# power.net
KiCad netlist of a schematic drawn in Altium Designer
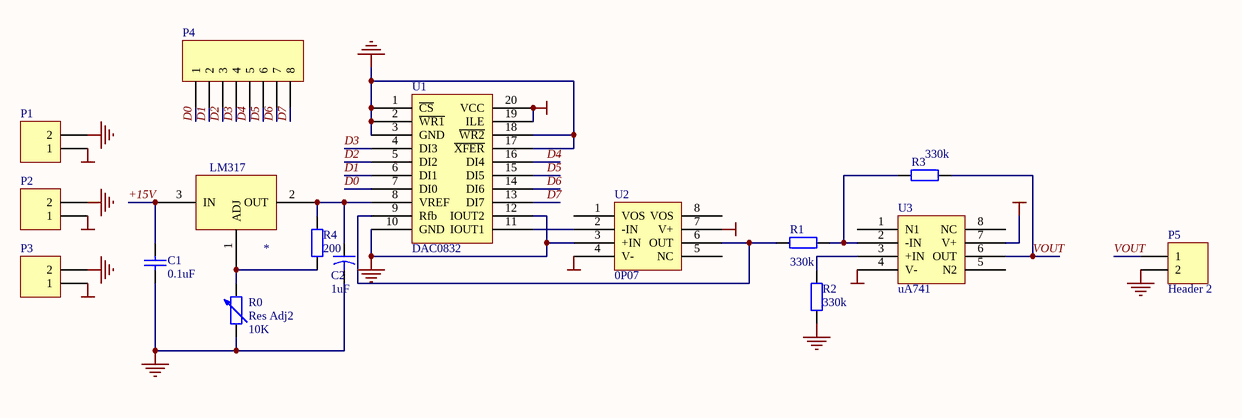
[diagram p0: power.SchDoc]

(export (version "E")
  (design (tool "Eeschema 10.0.6"))
  (components
    (comp (ref "C1")
      (value "0.1uF")
      (footprint "RAD-0.1")
      (description "Capacitor")
      (fields (field (name "PUBLISHER") "Altium Limited"))
      (libsource (lib "Miscellaneous Devices") (part "Cap"))
    )
    (comp (ref "C2")
      (value "1uF")
      (footprint "CAPR5-4X5")
      (description "Capacitor")
      (fields (field (name "PUBLISHER") "Altium Limited"))
      (libsource (lib "Miscellaneous Devices") (part "Cap2"))
    )
    (comp (ref "LM317") (value "*") (footprint "HDR1X3") (libsource (lib "My sch Library") (part "LM317")))
    (comp (ref "P1")
      (value "~")
      (footprint "HDR1X2")
      (description "Header, 2-Pin")
      (fields (field (name "PUBLISHER") "Altium Limited"))
      (libsource (lib "Miscellaneous Connectors") (part "Header 2"))
    )
    (comp (ref "P2")
      (value "~")
      (footprint "HDR1X2")
      (description "Header, 2-Pin")
      (fields (field (name "PUBLISHER") "Altium Limited"))
      (libsource (lib "Miscellaneous Connectors") (part "Header 2"))
    )
    (comp (ref "P3")
      (value "~")
      (footprint "HDR1X2")
      (description "Header, 2-Pin")
      (fields (field (name "PUBLISHER") "Altium Limited"))
      (libsource (lib "Miscellaneous Connectors") (part "Header 2"))
    )
    (comp (ref "P4")
      (value "~")
      (footprint "HDR1X8")
      (description "Header, 8-Pin")
      (fields (field (name "PUBLISHER") "Altium Limited"))
      (libsource (lib "Miscellaneous Connectors") (part "Header 8"))
    )
    (comp (ref "P5")
      (value "Header 2")
      (footprint "HDR1X2")
      (description "Header, 2-Pin")
      (fields (field (name "PUBLISHER") "Altium Limited"))
      (libsource (lib "") (part "Header 2_1"))
    )
    (comp (ref "R0")
      (value "Res Adj2")
      (footprint "AXIAL-0.6")
      (description "Variable Resistor")
      (fields (field (name "ALTIUM_VALUE") "10K") (field (name "PUBLISHER") "Altium Limited"))
      (libsource (lib "Miscellaneous Devices") (part "Res Adj2"))
    )
    (comp (ref "R1")
      (value "330k")
      (footprint "AXIAL-0.4")
      (description "Resistor")
      (fields (field (name "PUBLISHER") "Altium Limited"))
      (libsource (lib "") (part "Res2_1"))
    )
    (comp (ref "R2")
      (value "330k")
      (footprint "AXIAL-0.4")
      (description "Resistor")
      (fields (field (name "PUBLISHER") "Altium Limited"))
      (libsource (lib "Miscellaneous Devices") (part "Res2"))
    )
    (comp (ref "R3")
      (value "330k")
      (footprint "AXIAL-0.4")
      (description "Resistor")
      (fields (field (name "PUBLISHER") "Altium Limited"))
      (libsource (lib "") (part "Res2_1"))
    )
    (comp (ref "R4")
      (value "200")
      (footprint "AXIAL-0.4")
      (description "Resistor")
      (fields (field (name "PUBLISHER") "Altium Limited"))
      (libsource (lib "Miscellaneous Devices") (part "Res2"))
    )
    (comp (ref "U1")
      (value "DAC0832")
      (footprint "DIP-20")
      (libsource (lib "My sch Library") (part "DAC0832"))
    )
    (comp (ref "U2") (value "0P07") (footprint "DIP-8") (libsource (lib "My sch Library") (part "OP07")))
    (comp (ref "U3")
      (value "uA741")
      (footprint "DIP-8")
      (libsource (lib "My Integrated_Library") (part "uA741"))
    )
  )
  (nets
    (net (code "1") (name "+5V") (class "Default")
      (node (ref "P1") (pin "1") (pinfunction "1_1") (pintype "passive"))
      (node (ref "U1") (pin "19") (pinfunction "ILE_19") (pintype "passive"))
      (node (ref "U1") (pin "20") (pinfunction "VCC_20") (pintype "passive"))
    )
    (net (code "2") (name "+15V") (class "Default")
      (node (ref "C1") (pin "2") (pinfunction "2_2") (pintype "passive"))
      (node (ref "LM317") (pin "3") (pinfunction "IN_3") (pintype "passive"))
      (node (ref "P2") (pin "1") (pinfunction "1_1") (pintype "passive"))
      (node (ref "U2") (pin "7") (pinfunction "V+_7") (pintype "passive"))
      (node (ref "U3") (pin "7") (pinfunction "V+_7") (pintype "passive"))
    )
    (net (code "3") (name "-15V") (class "Default")
      (node (ref "P3") (pin "1") (pinfunction "1_1") (pintype "passive"))
      (node (ref "U2") (pin "4") (pinfunction "V-_4") (pintype "passive"))
      (node (ref "U3") (pin "4") (pinfunction "V-_4") (pintype "passive"))
    )
    (net (code "4") (name "/D0") (class "Default")
      (node (ref "P4") (pin "1") (pinfunction "1_1") (pintype "passive"))
      (node (ref "U1") (pin "7") (pinfunction "DI0_7") (pintype "passive"))
    )
    (net (code "5") (name "/D1") (class "Default")
      (node (ref "P4") (pin "2") (pinfunction "2_2") (pintype "passive"))
      (node (ref "U1") (pin "6") (pinfunction "DI1_6") (pintype "passive"))
    )
    (net (code "6") (name "/D2") (class "Default")
      (node (ref "P4") (pin "3") (pinfunction "3_3") (pintype "passive"))
      (node (ref "U1") (pin "5") (pinfunction "DI2_5") (pintype "passive"))
    )
    (net (code "7") (name "/D3") (class "Default")
      (node (ref "P4") (pin "4") (pinfunction "4_4") (pintype "passive"))
      (node (ref "U1") (pin "4") (pinfunction "DI3_4") (pintype "passive"))
    )
    (net (code "8") (name "/D4") (class "Default")
      (node (ref "P4") (pin "5") (pinfunction "5_5") (pintype "passive"))
      (node (ref "U1") (pin "16") (pinfunction "DI4_16") (pintype "passive"))
    )
    (net (code "9") (name "/D5") (class "Default")
      (node (ref "P4") (pin "6") (pinfunction "6_6") (pintype "passive"))
      (node (ref "U1") (pin "15") (pinfunction "DI5_15") (pintype "passive"))
    )
    (net (code "10") (name "/D6") (class "Default")
      (node (ref "P4") (pin "7") (pinfunction "7_7") (pintype "passive"))
      (node (ref "U1") (pin "14") (pinfunction "DI6_14") (pintype "passive"))
    )
    (net (code "11") (name "/D7") (class "Default")
      (node (ref "P4") (pin "8") (pinfunction "8_8") (pintype "passive"))
      (node (ref "U1") (pin "13") (pinfunction "DI7_13") (pintype "passive"))
    )
    (net (code "12") (name "/VOUT") (class "Default")
      (node (ref "P5") (pin "1") (pinfunction "1_1") (pintype "passive"))
      (node (ref "R3") (pin "2") (pinfunction "2_2") (pintype "passive"))
      (node (ref "U3") (pin "6") (pinfunction "OUT_6") (pintype "passive"))
    )
    (net (code "13") (name "GND") (class "Default")
      (node (ref "C1") (pin "1") (pinfunction "1_1") (pintype "passive"))
      (node (ref "C2") (pin "2") (pinfunction "2_2") (pintype "passive"))
      (node (ref "P1") (pin "2") (pinfunction "2_2") (pintype "passive"))
      (node (ref "P2") (pin "2") (pinfunction "2_2") (pintype "passive"))
      (node (ref "P3") (pin "2") (pinfunction "2_2") (pintype "passive"))
      (node (ref "P5") (pin "2") (pinfunction "2_2") (pintype "passive"))
      (node (ref "R0") (pin "1") (pinfunction "1_1") (pintype "passive"))
      (node (ref "R2") (pin "1") (pinfunction "1_1") (pintype "passive"))
      (node (ref "U1") (pin "1") (pinfunction "~{CS}_1") (pintype "passive"))
      (node (ref "U1") (pin "10") (pinfunction "GND_10") (pintype "passive"))
      (node (ref "U1") (pin "12") (pinfunction "IOUT2_12") (pintype "passive"))
      (node (ref "U1") (pin "17") (pinfunction "~{XFER}_17") (pintype "passive"))
      (node (ref "U1") (pin "18") (pinfunction "~{WR2}_18") (pintype "passive"))
      (node (ref "U1") (pin "2") (pinfunction "~{WR1}_2") (pintype "passive"))
      (node (ref "U1") (pin "3") (pinfunction "GND_3") (pintype "passive"))
      (node (ref "U2") (pin "3") (pinfunction "+IN_3") (pintype "passive"))
    )
    (net (code "14") (name "Net-(LM317-ADJ)") (class "Default")
      (node (ref "LM317") (pin "1") (pinfunction "ADJ_1") (pintype "passive"))
      (node (ref "R0") (pin "2") (pinfunction "2_2") (pintype "passive"))
      (node (ref "R4") (pin "1") (pinfunction "1_1") (pintype "passive"))
    )
    (net (code "15") (name "Net-(LM317-OUT)") (class "Default")
      (node (ref "C2") (pin "1") (pinfunction "1_1") (pintype "passive"))
      (node (ref "LM317") (pin "2") (pinfunction "OUT_2") (pintype "passive"))
      (node (ref "R4") (pin "2") (pinfunction "2_2") (pintype "passive"))
      (node (ref "U1") (pin "8") (pinfunction "VREF_8") (pintype "passive"))
    )
    (net (code "16") (name "Net-(U1-IOUT1)") (class "Default")
      (node (ref "U1") (pin "11") (pinfunction "IOUT1_11") (pintype "passive"))
      (node (ref "U2") (pin "2") (pinfunction "-IN_2") (pintype "passive"))
    )
    (net (code "17") (name "Net-(U1-Rfb)") (class "Default")
      (node (ref "R1") (pin "1") (pinfunction "1_1") (pintype "passive"))
      (node (ref "U1") (pin "9") (pinfunction "Rfb_9") (pintype "passive"))
      (node (ref "U2") (pin "6") (pinfunction "OUT_6") (pintype "passive"))
    )
    (net (code "18") (name "Net-(U3-+IN)") (class "Default")
      (node (ref "R2") (pin "2") (pinfunction "2_2") (pintype "passive"))
      (node (ref "U3") (pin "3") (pinfunction "+IN_3") (pintype "passive"))
    )
    (net (code "19") (name "Net-(U3--IN)") (class "Default")
      (node (ref "R1") (pin "2") (pinfunction "2_2") (pintype "passive"))
      (node (ref "R3") (pin "1") (pinfunction "1_1") (pintype "passive"))
      (node (ref "U3") (pin "2") (pinfunction "-IN_2") (pintype "passive"))
    )
    (net (code "20") (name "unconnected-(U2-NC-Pad5)") (class "Default")
      (node (ref "U2") (pin "5") (pinfunction "NC_5") (pintype "passive"))
    )
    (net (code "21") (name "unconnected-(U2-VOS-Pad1)") (class "Default")
      (node (ref "U2") (pin "1") (pinfunction "VOS_1") (pintype "passive"))
    )
    (net (code "22") (name "unconnected-(U2-VOS-Pad8)") (class "Default")
      (node (ref "U2") (pin "8") (pinfunction "VOS_8") (pintype "passive"))
    )
    (net (code "23") (name "unconnected-(U3-N1-Pad1)") (class "Default")
      (node (ref "U3") (pin "1") (pinfunction "N1_1") (pintype "passive"))
    )
    (net (code "24") (name "unconnected-(U3-N2-Pad5)") (class "Default")
      (node (ref "U3") (pin "5") (pinfunction "N2_5") (pintype "passive"))
    )
    (net (code "25") (name "unconnected-(U3-NC-Pad8)") (class "Default")
      (node (ref "U3") (pin "8") (pinfunction "NC_8") (pintype "passive"))
    )
  )
)
